# v0_4.net
KiCad netlist of a schematic drawn in EAGLE
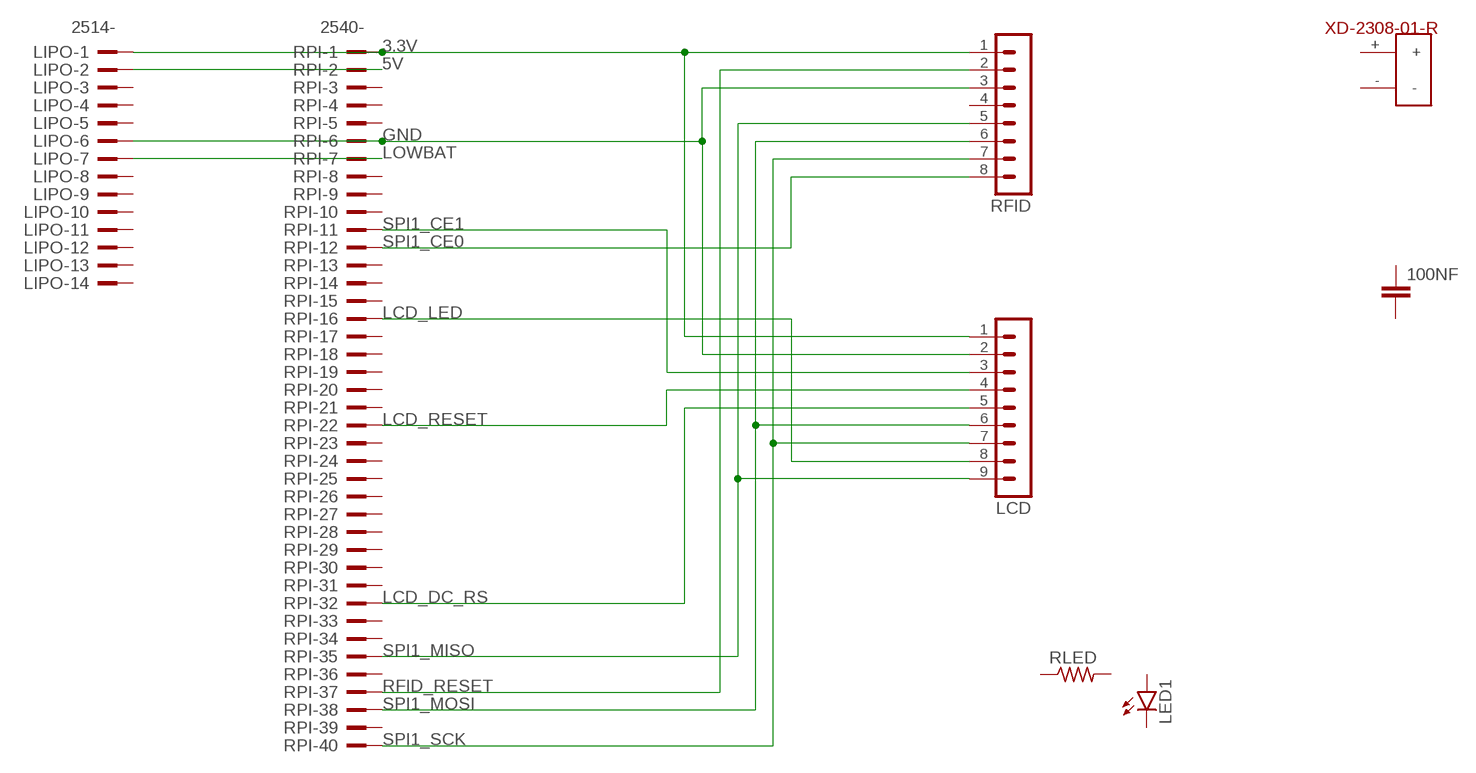
[diagram p0: schematic, sheet 1]

(export (version "E")
  (design (tool "Eeschema 10.0.6"))
  (components
    (comp (ref "100NF")
      (value "C-EU025-025X050")
      (footprint "eagle-import:C025-025X050")
      (libsource (lib "eagle-import") (part "C-EU025-025X050"))
    )
    (comp (ref "LCD")
      (value "MA09-1")
      (footprint "eagle-import:MA09-1")
      (libsource (lib "eagle-import") (part "MA09-1"))
    )
    (comp (ref "LED1")
      (value "LED3MM")
      (footprint "eagle-import:LED3MM")
      (libsource (lib "eagle-import") (part "LED3MM"))
    )
    (comp (ref "LIPO")
      (value "2514-")
      (footprint "eagle-import:PAK100_2500-14")
      (libsource (lib "eagle-import") (part "2514-"))
    )
    (comp (ref "RFID")
      (value "MA08-1")
      (footprint "eagle-import:MA08-1")
      (libsource (lib "eagle-import") (part "MA08-1"))
    )
    (comp (ref "RLED")
      (value "R-US_0204/5")
      (footprint "eagle-import:0204_5")
      (libsource (lib "eagle-import") (part "R-US_0204/5"))
    )
    (comp (ref "RPI")
      (value "2540-")
      (footprint "eagle-import:PAK100_2500-40")
      (libsource (lib "eagle-import") (part "2540-"))
    )
    (comp (ref "U$1")
      (value "XD-2308-01-R")
      (footprint "eagle-import:XD-2308-01-R")
      (libsource (lib "eagle-import") (part "XD-2308-01-R"))
    )
  )
  (nets
    (net (code "1") (name "/3.3V") (class "Default")
      (node (ref "LCD") (pin "1") (pinfunction "1_1") (pintype "passive"))
      (node (ref "LIPO") (pin "1") (pinfunction "KL_1") (pintype "passive"))
      (node (ref "RFID") (pin "1") (pinfunction "1_1") (pintype "passive"))
      (node (ref "RPI") (pin "1") (pinfunction "KL_1") (pintype "passive"))
    )
    (net (code "2") (name "/5V") (class "Default")
      (node (ref "LIPO") (pin "2") (pinfunction "KL_2") (pintype "passive"))
      (node (ref "RPI") (pin "2") (pinfunction "KL_2") (pintype "passive"))
    )
    (net (code "3") (name "/GND") (class "Default")
      (node (ref "LCD") (pin "2") (pinfunction "2_2") (pintype "passive"))
      (node (ref "LIPO") (pin "6") (pinfunction "KL_6") (pintype "passive"))
      (node (ref "RFID") (pin "3") (pinfunction "3_3") (pintype "passive"))
      (node (ref "RPI") (pin "6") (pinfunction "KL_6") (pintype "passive"))
    )
    (net (code "4") (name "/LCD_DC_RS") (class "Default")
      (node (ref "LCD") (pin "5") (pinfunction "5_5") (pintype "passive"))
      (node (ref "RPI") (pin "32") (pinfunction "KL_32") (pintype "passive"))
    )
    (net (code "5") (name "/LCD_LED") (class "Default")
      (node (ref "LCD") (pin "8") (pinfunction "8_8") (pintype "passive"))
      (node (ref "RPI") (pin "16") (pinfunction "KL_16") (pintype "passive"))
    )
    (net (code "6") (name "/LCD_RESET") (class "Default")
      (node (ref "LCD") (pin "4") (pinfunction "4_4") (pintype "passive"))
      (node (ref "RPI") (pin "22") (pinfunction "KL_22") (pintype "passive"))
    )
    (net (code "7") (name "/LOWBAT") (class "Default")
      (node (ref "LIPO") (pin "7") (pinfunction "KL_7") (pintype "passive"))
      (node (ref "RPI") (pin "7") (pinfunction "KL_7") (pintype "passive"))
    )
    (net (code "8") (name "/RFID_RESET") (class "Default")
      (node (ref "RFID") (pin "2") (pinfunction "2_2") (pintype "passive"))
      (node (ref "RPI") (pin "37") (pinfunction "KL_37") (pintype "passive"))
    )
    (net (code "9") (name "/SPI1_CE0") (class "Default")
      (node (ref "RFID") (pin "8") (pinfunction "8_8") (pintype "passive"))
      (node (ref "RPI") (pin "12") (pinfunction "KL_12") (pintype "passive"))
    )
    (net (code "10") (name "/SPI1_CE1") (class "Default")
      (node (ref "LCD") (pin "3") (pinfunction "3_3") (pintype "passive"))
      (node (ref "RPI") (pin "11") (pinfunction "KL_11") (pintype "passive"))
    )
    (net (code "11") (name "/SPI1_MISO") (class "Default")
      (node (ref "LCD") (pin "9") (pinfunction "9_9") (pintype "passive"))
      (node (ref "RFID") (pin "5") (pinfunction "5_5") (pintype "passive"))
      (node (ref "RPI") (pin "35") (pinfunction "KL_35") (pintype "passive"))
    )
    (net (code "12") (name "/SPI1_MOSI") (class "Default")
      (node (ref "LCD") (pin "6") (pinfunction "6_6") (pintype "passive"))
      (node (ref "RFID") (pin "6") (pinfunction "6_6") (pintype "passive"))
      (node (ref "RPI") (pin "38") (pinfunction "KL_38") (pintype "passive"))
    )
    (net (code "13") (name "/SPI1_SCK") (class "Default")
      (node (ref "LCD") (pin "7") (pinfunction "7_7") (pintype "passive"))
      (node (ref "RFID") (pin "7") (pinfunction "7_7") (pintype "passive"))
      (node (ref "RPI") (pin "40") (pinfunction "KL_40") (pintype "passive"))
    )
    (net (code "14") (name "unconnected-(100NF-Pad1)") (class "Default")
      (node (ref "100NF") (pin "1") (pinfunction "1_1") (pintype "passive"))
    )
    (net (code "15") (name "unconnected-(100NF-Pad2)") (class "Default")
      (node (ref "100NF") (pin "2") (pinfunction "2_2") (pintype "passive"))
    )
    (net (code "16") (name "unconnected-(LED1-C-PadK)") (class "Default")
      (node (ref "LED1") (pin "K") (pinfunction "C_K") (pintype "passive"))
    )
    (net (code "17") (name "unconnected-(LED1-PadA)") (class "Default")
      (node (ref "LED1") (pin "A") (pinfunction "A_A") (pintype "passive"))
    )
    (net (code "18") (name "unconnected-(LIPOB-KL-Pad10)") (class "Default")
      (node (ref "LIPO") (pin "10") (pinfunction "KL_10") (pintype "passive"))
    )
    (net (code "19") (name "unconnected-(LIPOC-KL-Pad11)") (class "Default")
      (node (ref "LIPO") (pin "11") (pinfunction "KL_11") (pintype "passive"))
    )
    (net (code "20") (name "unconnected-(LIPOD-KL-Pad12)") (class "Default")
      (node (ref "LIPO") (pin "12") (pinfunction "KL_12") (pintype "passive"))
    )
    (net (code "21") (name "unconnected-(LIPOE-KL-Pad13)") (class "Default")
      (node (ref "LIPO") (pin "13") (pinfunction "KL_13") (pintype "passive"))
    )
    (net (code "22") (name "unconnected-(LIPOF-KL-Pad14)") (class "Default")
      (node (ref "LIPO") (pin "14") (pinfunction "KL_14") (pintype "passive"))
    )
    (net (code "23") (name "unconnected-(LIPOH-KL-Pad3)") (class "Default")
      (node (ref "LIPO") (pin "3") (pinfunction "KL_3") (pintype "passive"))
    )
    (net (code "24") (name "unconnected-(LIPOI-KL-Pad4)") (class "Default")
      (node (ref "LIPO") (pin "4") (pinfunction "KL_4") (pintype "passive"))
    )
    (net (code "25") (name "unconnected-(LIPOJ-KL-Pad5)") (class "Default")
      (node (ref "LIPO") (pin "5") (pinfunction "KL_5") (pintype "passive"))
    )
    (net (code "26") (name "unconnected-(LIPOM-KL-Pad8)") (class "Default")
      (node (ref "LIPO") (pin "8") (pinfunction "KL_8") (pintype "passive"))
    )
    (net (code "27") (name "unconnected-(LIPON-KL-Pad9)") (class "Default")
      (node (ref "LIPO") (pin "9") (pinfunction "KL_9") (pintype "passive"))
    )
    (net (code "28") (name "unconnected-(RFID-Pad4)") (class "Default")
      (node (ref "RFID") (pin "4") (pinfunction "4_4") (pintype "passive"))
    )
    (net (code "29") (name "unconnected-(RLED-Pad1)") (class "Default")
      (node (ref "RLED") (pin "1") (pinfunction "1_1") (pintype "passive"))
    )
    (net (code "30") (name "unconnected-(RLED-Pad2)") (class "Default")
      (node (ref "RLED") (pin "2") (pinfunction "2_2") (pintype "passive"))
    )
    (net (code "31") (name "unconnected-(RPIAA-KL-Pad33)") (class "Default")
      (node (ref "RPI") (pin "33") (pinfunction "KL_33") (pintype "passive"))
    )
    (net (code "32") (name "unconnected-(RPIAB-KL-Pad34)") (class "Default")
      (node (ref "RPI") (pin "34") (pinfunction "KL_34") (pintype "passive"))
    )
    (net (code "33") (name "unconnected-(RPIAD-KL-Pad36)") (class "Default")
      (node (ref "RPI") (pin "36") (pinfunction "KL_36") (pintype "passive"))
    )
    (net (code "34") (name "unconnected-(RPIAG-KL-Pad39)") (class "Default")
      (node (ref "RPI") (pin "39") (pinfunction "KL_39") (pintype "passive"))
    )
    (net (code "35") (name "unconnected-(RPIAH-KL-Pad4)") (class "Default")
      (node (ref "RPI") (pin "4") (pinfunction "KL_4") (pintype "passive"))
    )
    (net (code "36") (name "unconnected-(RPIAJ-KL-Pad5)") (class "Default")
      (node (ref "RPI") (pin "5") (pinfunction "KL_5") (pintype "passive"))
    )
    (net (code "37") (name "unconnected-(RPIAM-KL-Pad8)") (class "Default")
      (node (ref "RPI") (pin "8") (pinfunction "KL_8") (pintype "passive"))
    )
    (net (code "38") (name "unconnected-(RPIAN-KL-Pad9)") (class "Default")
      (node (ref "RPI") (pin "9") (pinfunction "KL_9") (pintype "passive"))
    )
    (net (code "39") (name "unconnected-(RPIB-KL-Pad10)") (class "Default")
      (node (ref "RPI") (pin "10") (pinfunction "KL_10") (pintype "passive"))
    )
    (net (code "40") (name "unconnected-(RPIE-KL-Pad13)") (class "Default")
      (node (ref "RPI") (pin "13") (pinfunction "KL_13") (pintype "passive"))
    )
    (net (code "41") (name "unconnected-(RPIF-KL-Pad14)") (class "Default")
      (node (ref "RPI") (pin "14") (pinfunction "KL_14") (pintype "passive"))
    )
    (net (code "42") (name "unconnected-(RPIG-KL-Pad15)") (class "Default")
      (node (ref "RPI") (pin "15") (pinfunction "KL_15") (pintype "passive"))
    )
    (net (code "43") (name "unconnected-(RPII-KL-Pad17)") (class "Default")
      (node (ref "RPI") (pin "17") (pinfunction "KL_17") (pintype "passive"))
    )
    (net (code "44") (name "unconnected-(RPIJ-KL-Pad18)") (class "Default")
      (node (ref "RPI") (pin "18") (pinfunction "KL_18") (pintype "passive"))
    )
    (net (code "45") (name "unconnected-(RPIK-KL-Pad19)") (class "Default")
      (node (ref "RPI") (pin "19") (pinfunction "KL_19") (pintype "passive"))
    )
    (net (code "46") (name "unconnected-(RPIM-KL-Pad20)") (class "Default")
      (node (ref "RPI") (pin "20") (pinfunction "KL_20") (pintype "passive"))
    )
    (net (code "47") (name "unconnected-(RPIN-KL-Pad21)") (class "Default")
      (node (ref "RPI") (pin "21") (pinfunction "KL_21") (pintype "passive"))
    )
    (net (code "48") (name "unconnected-(RPIP-KL-Pad23)") (class "Default")
      (node (ref "RPI") (pin "23") (pinfunction "KL_23") (pintype "passive"))
    )
    (net (code "49") (name "unconnected-(RPIQ-KL-Pad24)") (class "Default")
      (node (ref "RPI") (pin "24") (pinfunction "KL_24") (pintype "passive"))
    )
    (net (code "50") (name "unconnected-(RPIR-KL-Pad25)") (class "Default")
      (node (ref "RPI") (pin "25") (pinfunction "KL_25") (pintype "passive"))
    )
    (net (code "51") (name "unconnected-(RPIS-KL-Pad26)") (class "Default")
      (node (ref "RPI") (pin "26") (pinfunction "KL_26") (pintype "passive"))
    )
    (net (code "52") (name "unconnected-(RPIT-KL-Pad27)") (class "Default")
      (node (ref "RPI") (pin "27") (pinfunction "KL_27") (pintype "passive"))
    )
    (net (code "53") (name "unconnected-(RPIU-KL-Pad28)") (class "Default")
      (node (ref "RPI") (pin "28") (pinfunction "KL_28") (pintype "passive"))
    )
    (net (code "54") (name "unconnected-(RPIV-KL-Pad29)") (class "Default")
      (node (ref "RPI") (pin "29") (pinfunction "KL_29") (pintype "passive"))
    )
    (net (code "55") (name "unconnected-(RPIW-KL-Pad3)") (class "Default")
      (node (ref "RPI") (pin "3") (pinfunction "KL_3") (pintype "passive"))
    )
    (net (code "56") (name "unconnected-(RPIX-KL-Pad30)") (class "Default")
      (node (ref "RPI") (pin "30") (pinfunction "KL_30") (pintype "passive"))
    )
    (net (code "57") (name "unconnected-(RPIY-KL-Pad31)") (class "Default")
      (node (ref "RPI") (pin "31") (pinfunction "KL_31") (pintype "passive"))
    )
    (net (code "58") (name "unconnected-(U$1-Pad+)") (class "Default")
      (node (ref "U$1") (pin "+") (pinfunction "+_+") (pintype "input"))
    )
    (net (code "59") (name "unconnected-(U$1-Pad-)") (class "Default")
      (node (ref "U$1") (pin "-") (pinfunction "-_-") (pintype "output"))
    )
  )
)
